# Cam_HDMI.net
KiCad netlist of a schematic drawn in Altium Designer
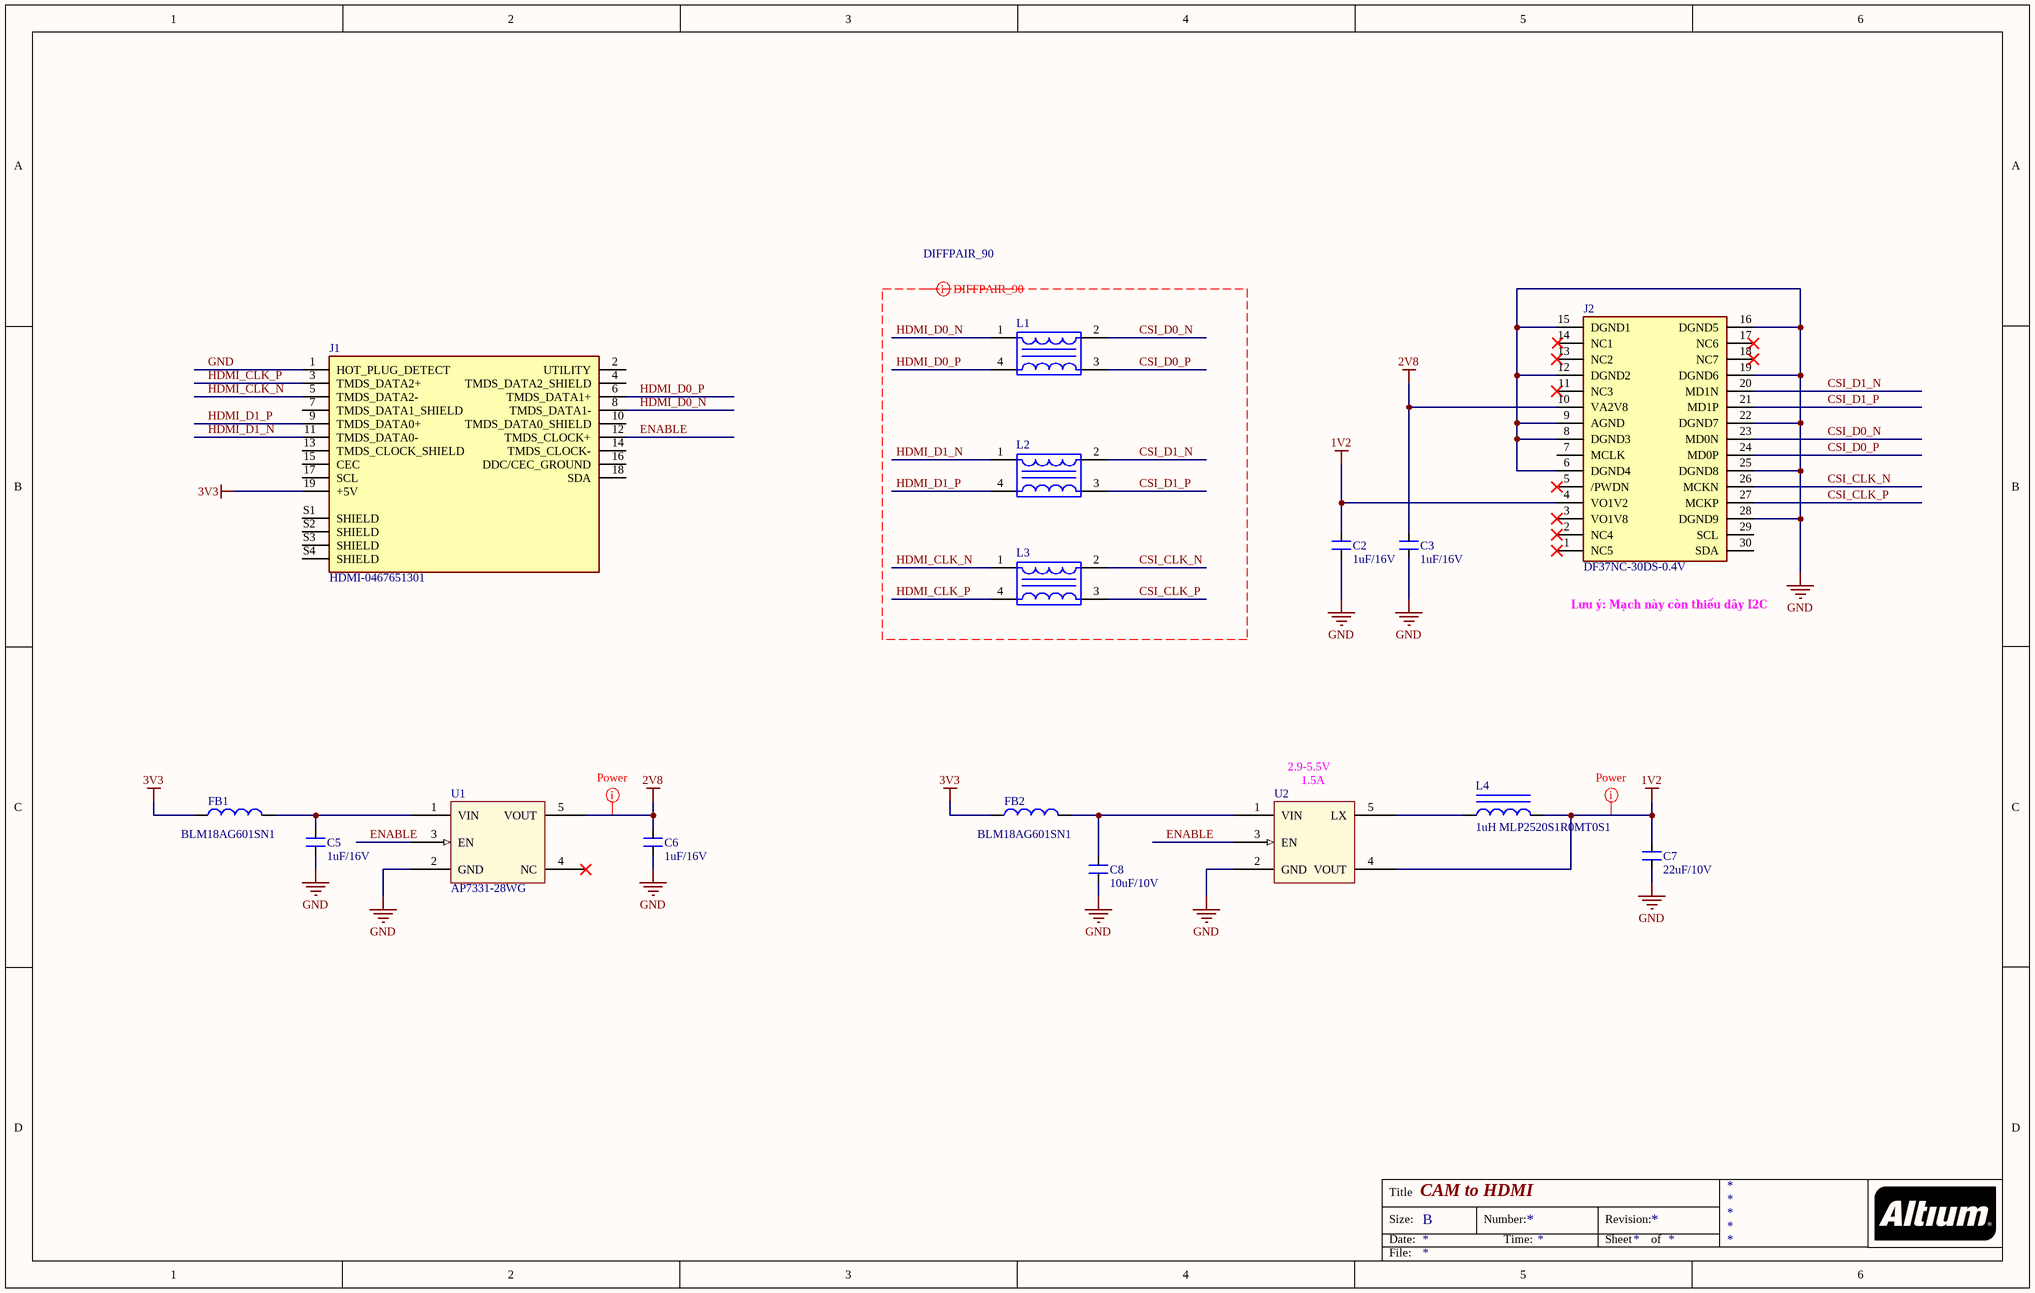
[diagram p0: Cam_HDMI.SchDoc]

(export (version "E")
  (design (tool "Eeschema 10.0.6"))
  (components
    (comp (ref "C2")
      (value "1uF/16V")
      (footprint "CAP_CERA_C1608(CC0603INCH)")
      (description "0.1µF ±5% 16V Ceramic Capacitor X7R 0805 (2012 Metric)")
      (libsource (lib "PiCamUsbC") (part "Cap Ceramic SMD"))
    )
    (comp (ref "C3")
      (value "1uF/16V")
      (footprint "CAP_CERA_C1608(CC0603INCH)")
      (description "1µF ±10% 16V Ceramic Capacitor X7R 0603 (1608 Metric)")
      (libsource (lib "PiCamUsbC") (part "Cap Ceramic SMD"))
    )
    (comp (ref "C5")
      (value "1uF/16V")
      (footprint "CAP_CERA_C1608(CC0603INCH)")
      (description "0.1µF ±5% 16V Ceramic Capacitor X7R 0805 (2012 Metric)")
      (libsource (lib "PiCamUsbC") (part "Cap Ceramic SMD"))
    )
    (comp (ref "C6")
      (value "1uF/16V")
      (footprint "CAP_CERA_C1608(CC0603INCH)")
      (description "0.1µF ±5% 16V Ceramic Capacitor X7R 0805 (2012 Metric)")
      (libsource (lib "PiCamUsbC") (part "Cap Ceramic SMD"))
    )
    (comp (ref "C7")
      (value "22uF/10V")
      (footprint "CAP_CERA_C1608(CC0603INCH)")
      (description "0.1µF ±5% 16V Ceramic Capacitor X7R 0805 (2012 Metric)")
      (libsource (lib "PiCamUsbC") (part "Cap Ceramic SMD"))
    )
    (comp (ref "C8")
      (value "10uF/10V")
      (footprint "CAP_CERA_C1608(CC0603INCH)")
      (description "0.1µF ±5% 16V Ceramic Capacitor X7R 0805 (2012 Metric)")
      (libsource (lib "PiCamUsbC") (part "Cap Ceramic SMD"))
    )
    (comp (ref "FB1")
      (value "BLM18AG601SN1")
      (footprint "L0603")
      (description "600@100MHz")
      (libsource (lib "PiCamUsbC") (part "Ferrite Bead"))
    )
    (comp (ref "FB2")
      (value "BLM18AG601SN1")
      (footprint "L0603")
      (description "600@100MHz")
      (libsource (lib "PiCamUsbC") (part "Ferrite Bead"))
    )
    (comp (ref "J1")
      (value "HDMI-0467651301")
      (footprint "HDMI_MOLEX_0467650301")
      (description "HDMI - Micro Receptacle Connector 19 Position Surface Mount, Right Angle")
      (fields (field (name "MF") "Molex") (field (name "MP") "0467650301"))
      (libsource (lib "lpson") (part "HDMI-0467651301"))
    )
    (comp (ref "J2")
      (value "DF37NC-30DS-0.4V")
      (footprint "DF37NC-30DS-0.4V")
      (libsource (lib "PiCamUsbC") (part "DF37NC-30DS-0.4V"))
    )
    (comp (ref "L1")
      (value "~")
      (footprint "DLP11SN900HL2L")
      (libsource (lib "PiCamUsbC") (part "DLP11SN900HL2L"))
    )
    (comp (ref "L2")
      (value "~")
      (footprint "DLP11SN900HL2L")
      (libsource (lib "PiCamUsbC") (part "DLP11SN900HL2L"))
    )
    (comp (ref "L3")
      (value "~")
      (footprint "DLP11SN900HL2L")
      (libsource (lib "PiCamUsbC") (part "DLP11SN900HL2L"))
    )
    (comp (ref "L4")
      (value "1uH MLP2520S1R0MT0S1")
      (footprint "L 2520mm")
      (description "CIGT252008LM2R2MNE,  2.2µH2A, 2520")
      (libsource (lib "PiCamUsbC") (part "CIGT252008LM2R2MNE"))
    )
    (comp (ref "U1")
      (value "AP7331-28WG")
      (footprint "SOT25")
      (description "IC REG LINEAR 2.5V 150MA SOT25")
      (libsource (lib "PiCamUsbC") (part "AP7331-28WG"))
    )
    (comp (ref "U2")
      (value "~")
      (footprint "SOT25")
      (description "IC REG BUCK 1.2V 1.5A TSOT23-5")
      (libsource (lib "lpson") (part "SC189CSKTRT"))
    )
  )
  (nets
    (net (code "1") (name "/CSI_CLK_N") (class "Default")
      (node (ref "J2") (pin "26") (pinfunction "MCKN_26") (pintype "passive"))
      (node (ref "L3") (pin "2") (pinfunction "2_2") (pintype "passive"))
    )
    (net (code "2") (name "/CSI_CLK_P") (class "Default")
      (node (ref "J2") (pin "27") (pinfunction "MCKP_27") (pintype "passive"))
      (node (ref "L3") (pin "3") (pinfunction "3_3") (pintype "passive"))
    )
    (net (code "3") (name "/CSI_D0_N") (class "Default")
      (node (ref "J2") (pin "23") (pinfunction "MD0N_23") (pintype "passive"))
      (node (ref "L1") (pin "2") (pinfunction "2_2") (pintype "passive"))
    )
    (net (code "4") (name "/CSI_D0_P") (class "Default")
      (node (ref "J2") (pin "24") (pinfunction "MD0P_24") (pintype "passive"))
      (node (ref "L1") (pin "3") (pinfunction "3_3") (pintype "passive"))
    )
    (net (code "5") (name "/CSI_D1_N") (class "Default")
      (node (ref "J2") (pin "20") (pinfunction "MD1N_20") (pintype "passive"))
      (node (ref "L2") (pin "2") (pinfunction "2_2") (pintype "passive"))
    )
    (net (code "6") (name "/CSI_D1_P") (class "Default")
      (node (ref "J2") (pin "21") (pinfunction "MD1P_21") (pintype "passive"))
      (node (ref "L2") (pin "3") (pinfunction "3_3") (pintype "passive"))
    )
    (net (code "7") (name "/ENABLE") (class "Default")
      (node (ref "J1") (pin "12") (pinfunction "TMDS_CLOCK+_12") (pintype "passive"))
      (node (ref "U1") (pin "3") (pinfunction "EN_3") (pintype "input"))
      (node (ref "U2") (pin "3") (pinfunction "EN_3") (pintype "input"))
    )
    (net (code "8") (name "/HDMI_CLK_N") (class "Default")
      (node (ref "J1") (pin "5") (pinfunction "TMDS_DATA2-_5") (pintype "passive"))
      (node (ref "L3") (pin "1") (pinfunction "1_1") (pintype "passive"))
    )
    (net (code "9") (name "/HDMI_CLK_P") (class "Default")
      (node (ref "J1") (pin "3") (pinfunction "TMDS_DATA2+_3") (pintype "passive"))
      (node (ref "L3") (pin "4") (pinfunction "4_4") (pintype "passive"))
    )
    (net (code "10") (name "/HDMI_D0_N") (class "Default")
      (node (ref "J1") (pin "8") (pinfunction "TMDS_DATA1-_8") (pintype "passive"))
      (node (ref "L1") (pin "1") (pinfunction "1_1") (pintype "passive"))
    )
    (net (code "11") (name "/HDMI_D0_P") (class "Default")
      (node (ref "J1") (pin "6") (pinfunction "TMDS_DATA1+_6") (pintype "passive"))
      (node (ref "L1") (pin "4") (pinfunction "4_4") (pintype "passive"))
    )
    (net (code "12") (name "/HDMI_D1_N") (class "Default")
      (node (ref "J1") (pin "11") (pinfunction "TMDS_DATA0-_11") (pintype "passive"))
      (node (ref "L2") (pin "1") (pinfunction "1_1") (pintype "passive"))
    )
    (net (code "13") (name "/HDMI_D1_P") (class "Default")
      (node (ref "J1") (pin "9") (pinfunction "TMDS_DATA0+_9") (pintype "passive"))
      (node (ref "L2") (pin "4") (pinfunction "4_4") (pintype "passive"))
    )
    (net (code "14") (name "1V2") (class "Default")
      (node (ref "C2") (pin "1") (pinfunction "1_1") (pintype "passive"))
      (node (ref "C7") (pin "1") (pinfunction "1_1") (pintype "passive"))
      (node (ref "J2") (pin "4") (pinfunction "VO1V2_4") (pintype "passive"))
      (node (ref "L4") (pin "2") (pinfunction "2_2") (pintype "passive"))
      (node (ref "U2") (pin "4") (pinfunction "VOUT_4") (pintype "power_in"))
    )
    (net (code "15") (name "2V8") (class "Default")
      (node (ref "C3") (pin "1") (pinfunction "1_1") (pintype "passive"))
      (node (ref "C6") (pin "1") (pinfunction "1_1") (pintype "passive"))
      (node (ref "J2") (pin "10") (pinfunction "VA2V8_10") (pintype "passive"))
      (node (ref "U1") (pin "5") (pinfunction "VOUT_5") (pintype "power_in"))
    )
    (net (code "16") (name "3V3") (class "Default")
      (node (ref "FB1") (pin "1") (pinfunction "1_1") (pintype "passive"))
      (node (ref "FB2") (pin "1") (pinfunction "1_1") (pintype "passive"))
      (node (ref "J1") (pin "19") (pinfunction "+5V_19") (pintype "passive"))
    )
    (net (code "17") (name "GND") (class "Default")
      (node (ref "C2") (pin "2") (pinfunction "2_2") (pintype "passive"))
      (node (ref "C3") (pin "2") (pinfunction "2_2") (pintype "passive"))
      (node (ref "C5") (pin "2") (pinfunction "2_2") (pintype "passive"))
      (node (ref "C6") (pin "2") (pinfunction "2_2") (pintype "passive"))
      (node (ref "C7") (pin "2") (pinfunction "2_2") (pintype "passive"))
      (node (ref "C8") (pin "2") (pinfunction "2_2") (pintype "passive"))
      (node (ref "J1") (pin "1") (pinfunction "HOT_PLUG_DETECT_1") (pintype "passive"))
      (node (ref "J2") (pin "12") (pinfunction "DGND2_12") (pintype "passive"))
      (node (ref "J2") (pin "15") (pinfunction "DGND1_15") (pintype "passive"))
      (node (ref "J2") (pin "16") (pinfunction "DGND5_16") (pintype "passive"))
      (node (ref "J2") (pin "19") (pinfunction "DGND6_19") (pintype "passive"))
      (node (ref "J2") (pin "22") (pinfunction "DGND7_22") (pintype "passive"))
      (node (ref "J2") (pin "25") (pinfunction "DGND8_25") (pintype "passive"))
      (node (ref "J2") (pin "28") (pinfunction "DGND9_28") (pintype "passive"))
      (node (ref "J2") (pin "6") (pinfunction "DGND4_6") (pintype "passive"))
      (node (ref "J2") (pin "8") (pinfunction "DGND3_8") (pintype "passive"))
      (node (ref "J2") (pin "9") (pinfunction "AGND_9") (pintype "passive"))
      (node (ref "U1") (pin "2") (pinfunction "GND_2") (pintype "power_in"))
      (node (ref "U2") (pin "2") (pinfunction "GND_2") (pintype "power_in"))
    )
    (net (code "18") (name "Net-(U1-VIN)") (class "Default")
      (node (ref "C5") (pin "1") (pinfunction "1_1") (pintype "passive"))
      (node (ref "FB1") (pin "2") (pinfunction "2_2") (pintype "passive"))
      (node (ref "U1") (pin "1") (pinfunction "VIN_1") (pintype "power_in"))
    )
    (net (code "19") (name "Net-(U2-LX)") (class "Default")
      (node (ref "L4") (pin "1") (pinfunction "1_1") (pintype "passive"))
      (node (ref "U2") (pin "5") (pinfunction "LX_5") (pintype "power_in"))
    )
    (net (code "20") (name "Net-(U2-VIN)") (class "Default")
      (node (ref "C8") (pin "1") (pinfunction "1_1") (pintype "passive"))
      (node (ref "FB2") (pin "2") (pinfunction "2_2") (pintype "passive"))
      (node (ref "U2") (pin "1") (pinfunction "VIN_1") (pintype "power_in"))
    )
    (net (code "21") (name "unconnected-(J1-CEC-Pad15)") (class "Default")
      (node (ref "J1") (pin "15") (pinfunction "CEC_15") (pintype "passive"))
    )
    (net (code "22") (name "unconnected-(J1-DDC{slash}CEC_GROUND-Pad16)") (class "Default")
      (node (ref "J1") (pin "16") (pinfunction "DDC/CEC_GROUND_16") (pintype "passive"))
    )
    (net (code "23") (name "unconnected-(J1-SCL-Pad17)") (class "Default")
      (node (ref "J1") (pin "17") (pinfunction "SCL_17") (pintype "passive"))
    )
    (net (code "24") (name "unconnected-(J1-SDA-Pad18)") (class "Default")
      (node (ref "J1") (pin "18") (pinfunction "SDA_18") (pintype "passive"))
    )
    (net (code "25") (name "unconnected-(J1-SHIELD-PadS1)") (class "Default")
      (node (ref "J1") (pin "S1") (pinfunction "SHIELD_S1") (pintype "passive"))
    )
    (net (code "26") (name "unconnected-(J1-SHIELD-PadS2)") (class "Default")
      (node (ref "J1") (pin "S2") (pinfunction "SHIELD_S2") (pintype "passive"))
    )
    (net (code "27") (name "unconnected-(J1-SHIELD-PadS3)") (class "Default")
      (node (ref "J1") (pin "S3") (pinfunction "SHIELD_S3") (pintype "passive"))
    )
    (net (code "28") (name "unconnected-(J1-SHIELD-PadS4)") (class "Default")
      (node (ref "J1") (pin "S4") (pinfunction "SHIELD_S4") (pintype "passive"))
    )
    (net (code "29") (name "unconnected-(J1-TMDS_CLOCK--Pad14)") (class "Default")
      (node (ref "J1") (pin "14") (pinfunction "TMDS_CLOCK-_14") (pintype "passive"))
    )
    (net (code "30") (name "unconnected-(J1-TMDS_CLOCK_SHIELD-Pad13)") (class "Default")
      (node (ref "J1") (pin "13") (pinfunction "TMDS_CLOCK_SHIELD_13") (pintype "passive"))
    )
    (net (code "31") (name "unconnected-(J1-TMDS_DATA0_SHIELD-Pad10)") (class "Default")
      (node (ref "J1") (pin "10") (pinfunction "TMDS_DATA0_SHIELD_10") (pintype "passive"))
    )
    (net (code "32") (name "unconnected-(J1-TMDS_DATA1_SHIELD-Pad7)") (class "Default")
      (node (ref "J1") (pin "7") (pinfunction "TMDS_DATA1_SHIELD_7") (pintype "passive"))
    )
    (net (code "33") (name "unconnected-(J1-TMDS_DATA2_SHIELD-Pad4)") (class "Default")
      (node (ref "J1") (pin "4") (pinfunction "TMDS_DATA2_SHIELD_4") (pintype "passive"))
    )
    (net (code "34") (name "unconnected-(J1-UTILITY-Pad2)") (class "Default")
      (node (ref "J1") (pin "2") (pinfunction "UTILITY_2") (pintype "passive"))
    )
    (net (code "35") (name "unconnected-(J2-MCLK-Pad7)") (class "Default")
      (node (ref "J2") (pin "7") (pinfunction "MCLK_7") (pintype "passive"))
    )
    (net (code "36") (name "unconnected-(J2-NC1-Pad14)") (class "Default")
      (node (ref "J2") (pin "14") (pinfunction "NC1_14") (pintype "passive"))
    )
    (net (code "37") (name "unconnected-(J2-NC2-Pad13)") (class "Default")
      (node (ref "J2") (pin "13") (pinfunction "NC2_13") (pintype "passive+no_connect"))
    )
    (net (code "38") (name "unconnected-(J2-NC3-Pad11)") (class "Default")
      (node (ref "J2") (pin "11") (pinfunction "NC3_11") (pintype "passive+no_connect"))
    )
    (net (code "39") (name "unconnected-(J2-NC4-Pad2)") (class "Default")
      (node (ref "J2") (pin "2") (pinfunction "NC4_2") (pintype "passive+no_connect"))
    )
    (net (code "40") (name "unconnected-(J2-NC5-Pad1)") (class "Default")
      (node (ref "J2") (pin "1") (pinfunction "NC5_1") (pintype "passive+no_connect"))
    )
    (net (code "41") (name "unconnected-(J2-NC6-Pad17)") (class "Default")
      (node (ref "J2") (pin "17") (pinfunction "NC6_17") (pintype "passive+no_connect"))
    )
    (net (code "42") (name "unconnected-(J2-NC7-Pad18)") (class "Default")
      (node (ref "J2") (pin "18") (pinfunction "NC7_18") (pintype "passive+no_connect"))
    )
    (net (code "43") (name "unconnected-(J2-SCL-Pad29)") (class "Default")
      (node (ref "J2") (pin "29") (pinfunction "SCL_29") (pintype "passive"))
    )
    (net (code "44") (name "unconnected-(J2-SDA-Pad30)") (class "Default")
      (node (ref "J2") (pin "30") (pinfunction "SDA_30") (pintype "passive"))
    )
    (net (code "45") (name "unconnected-(J2-VO1V8-Pad3)") (class "Default")
      (node (ref "J2") (pin "3") (pinfunction "VO1V8_3") (pintype "passive+no_connect"))
    )
    (net (code "46") (name "unconnected-(J2-{slash}PWDN-Pad5)") (class "Default")
      (node (ref "J2") (pin "5") (pinfunction "/PWDN_5") (pintype "passive+no_connect"))
    )
    (net (code "47") (name "unconnected-(U1-NC-Pad4)") (class "Default")
      (node (ref "U1") (pin "4") (pinfunction "NC_4") (pintype "power_in+no_connect"))
    )
  )
)
